# BUTTON_LED.net
KiCad netlist of a schematic drawn in Altium Designer
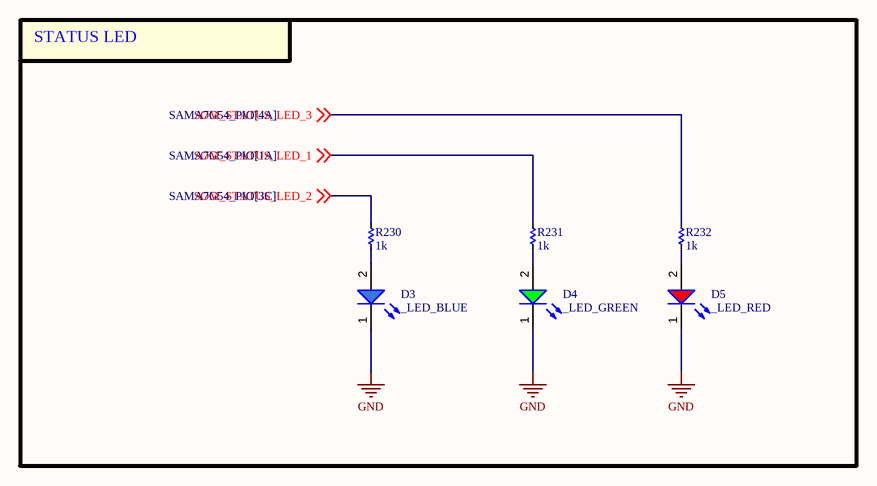
[diagram p0: BUTTON_LED.SchDoc]

(export (version "E")
  (design (tool "Eeschema 10.0.6"))
  (components
    (comp (ref "D3")
      (value "_LED_BLUE")
      (footprint "LED_0603")
      (description "LED BLUE CLEAR 0603 SMD")
      (libsource (lib "IFBschelib") (part "LED_BLUE"))
    )
    (comp (ref "D4")
      (value "_LED_GREEN")
      (footprint "LED_0603")
      (description "LED GREEN CLEAR 0603 SMD")
      (libsource (lib "IFBschelib") (part "LED_GREEN"))
    )
    (comp (ref "D5")
      (value "_LED_RED")
      (footprint "LED_0603")
      (description "LED RED CLEAR 0603 SMD")
      (libsource (lib "IFBschelib") (part "LED_RED"))
    )
    (comp (ref "R230")
      (value "1k")
      (footprint "RES_C_1005x30_L")
      (description "RES")
      (libsource (lib "LABLIB") (part "_RES_B_2"))
    )
    (comp (ref "R231")
      (value "1k")
      (footprint "RES_C_1005x30_L")
      (description "RES")
      (libsource (lib "LABLIB") (part "_RES_B_2"))
    )
    (comp (ref "R232")
      (value "1k")
      (footprint "RES_C_1005x30_L")
      (description "RES")
      (libsource (lib "LABLIB") (part "_RES_B_2"))
    )
  )
  (nets
    (net (code "1") (name "GND") (class "Default")
      (node (ref "D3") (pin "1") (pinfunction "K_1") (pintype "passive"))
      (node (ref "D4") (pin "1") (pinfunction "K_1") (pintype "passive"))
      (node (ref "D5") (pin "1") (pinfunction "K_1") (pintype "passive"))
    )
    (net (code "2") (name "Net-(D3-A)") (class "Default")
      (node (ref "D3") (pin "2") (pinfunction "A_2") (pintype "passive"))
      (node (ref "R230") (pin "1") (pinfunction "1_1") (pintype "passive"))
    )
    (net (code "3") (name "Net-(D4-A)") (class "Default")
      (node (ref "D4") (pin "2") (pinfunction "A_2") (pintype "passive"))
      (node (ref "R231") (pin "1") (pinfunction "1_1") (pintype "passive"))
    )
    (net (code "4") (name "Net-(D5-A)") (class "Default")
      (node (ref "D5") (pin "2") (pinfunction "A_2") (pintype "passive"))
      (node (ref "R232") (pin "1") (pinfunction "1_1") (pintype "passive"))
    )
    (net (code "5") (name "SOM_STATUS_LED_1") (class "Default")
      (node (ref "R231") (pin "2") (pinfunction "2_2") (pintype "passive"))
    )
    (net (code "6") (name "SOM_STATUS_LED_2") (class "Default")
      (node (ref "R230") (pin "2") (pinfunction "2_2") (pintype "passive"))
    )
    (net (code "7") (name "SOM_STATUS_LED_3") (class "Default")
      (node (ref "R232") (pin "2") (pinfunction "2_2") (pintype "passive"))
    )
  )
)
